# PCB_Assignment.net
KiCad netlist of a schematic drawn in EAGLE
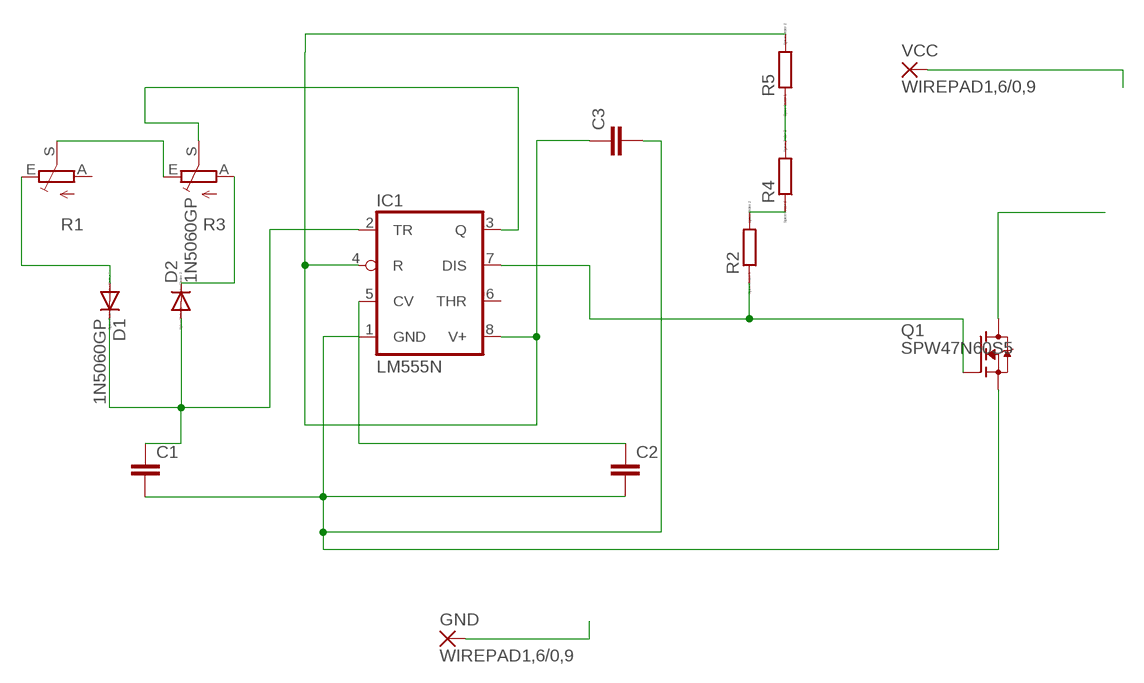
[diagram p0: schematic, sheet 1]

(export (version "E")
  (design (tool "Eeschema 10.0.6"))
  (components
    (comp (ref "C1")
      (value "C2.5/2")
      (footprint "eagle-import:C2.5-2")
      (libsource (lib "eagle-import") (part "C2.5/2"))
    )
    (comp (ref "C2")
      (value "C2.5/2")
      (footprint "eagle-import:C2.5-2")
      (libsource (lib "eagle-import") (part "C2.5/2"))
    )
    (comp (ref "C3")
      (value "C2.5/2")
      (footprint "eagle-import:C2.5-2")
      (libsource (lib "eagle-import") (part "C2.5/2"))
    )
    (comp (ref "D1")
      (value "1N5060GP")
      (footprint "eagle-import:DO15-12")
      (libsource (lib "eagle-import") (part "1N5060GP"))
    )
    (comp (ref "D2")
      (value "1N5060GP")
      (footprint "eagle-import:DO15-12")
      (libsource (lib "eagle-import") (part "1N5060GP"))
    )
    (comp (ref "GND")
      (value "WIREPAD1,6/0,9")
      (footprint "eagle-import:1,6_0,9")
      (libsource (lib "eagle-import") (part "WIREPAD1,6/0,9"))
    )
    (comp (ref "IC1")
      (value "LM555N")
      (footprint "eagle-import:DIL08")
      (libsource (lib "eagle-import") (part "555NLM"))
    )
    (comp (ref "Q1")
      (value "SPW47N60S5")
      (footprint "eagle-import:P-TO247")
      (libsource (lib "eagle-import") (part "SPW47N60S5"))
    )
    (comp (ref "R1")
      (value "TRIM_EU-B64Y")
      (footprint "eagle-import:B64Y")
      (libsource (lib "eagle-import") (part "TRIM_EU-B64Y"))
    )
    (comp (ref "R2")
      (value "R0204/7")
      (footprint "eagle-import:0204_7")
      (libsource (lib "eagle-import") (part "R0204/7"))
    )
    (comp (ref "R3")
      (value "TRIM_EU-B64Y")
      (footprint "eagle-import:B64Y")
      (libsource (lib "eagle-import") (part "TRIM_EU-B64Y"))
    )
    (comp (ref "R4")
      (value "R0204/7")
      (footprint "eagle-import:0204_7")
      (libsource (lib "eagle-import") (part "R0204/7"))
    )
    (comp (ref "R5")
      (value "R0204/7")
      (footprint "eagle-import:0204_7")
      (libsource (lib "eagle-import") (part "R0204/7"))
    )
    (comp (ref "VCC")
      (value "WIREPAD1,6/0,9")
      (footprint "eagle-import:1,6_0,9")
      (libsource (lib "eagle-import") (part "WIREPAD1,6/0,9"))
    )
  )
  (nets
    (net (code "1") (name "/GND") (class "Default")
      (node (ref "C1") (pin "2") (pinfunction "2_2") (pintype "passive"))
      (node (ref "C2") (pin "2") (pinfunction "2_2") (pintype "passive"))
      (node (ref "C3") (pin "2") (pinfunction "2_2") (pintype "passive"))
      (node (ref "GND") (pin "1") (pinfunction "P_1") (pintype "passive"))
      (node (ref "IC1") (pin "1") (pinfunction "GND_1") (pintype "power_in"))
      (node (ref "Q1") (pin "3") (pinfunction "S_3") (pintype "passive"))
    )
    (net (code "2") (name "/VCC") (class "Default")
      (node (ref "C3") (pin "1") (pinfunction "1_1") (pintype "passive"))
      (node (ref "IC1") (pin "4") (pinfunction "R_4") (pintype "input"))
      (node (ref "IC1") (pin "8") (pinfunction "V+_8") (pintype "power_in"))
      (node (ref "R5") (pin "2") (pinfunction "2_2") (pintype "passive"))
      (node (ref "VCC") (pin "1") (pinfunction "P_1") (pintype "passive"))
    )
    (net (code "3") (name "Net-(D1-PadA)") (class "Default")
      (node (ref "D1") (pin "A") (pinfunction "A_A") (pintype "passive"))
      (node (ref "R1") (pin "E") (pinfunction "E_E") (pintype "passive"))
    )
    (net (code "4") (name "Net-(D2-PadC)") (class "Default")
      (node (ref "D2") (pin "C") (pinfunction "C_C") (pintype "passive"))
      (node (ref "R3") (pin "A") (pinfunction "A_A") (pintype "passive"))
    )
    (net (code "5") (name "Net-(IC1-CV)") (class "Default")
      (node (ref "C2") (pin "1") (pinfunction "1_1") (pintype "passive"))
      (node (ref "IC1") (pin "5") (pinfunction "CV_5") (pintype "input"))
    )
    (net (code "6") (name "Net-(IC1-DIS)") (class "Default")
      (node (ref "IC1") (pin "7") (pinfunction "DIS_7") (pintype "input"))
      (node (ref "Q1") (pin "1") (pinfunction "G_1") (pintype "passive"))
      (node (ref "R2") (pin "1") (pinfunction "1_1") (pintype "passive"))
    )
    (net (code "7") (name "Net-(IC1-Q)") (class "Default")
      (node (ref "IC1") (pin "3") (pinfunction "Q_3") (pintype "output"))
      (node (ref "R3") (pin "S") (pinfunction "S_S") (pintype "passive"))
    )
    (net (code "8") (name "Net-(IC1-TR)") (class "Default")
      (node (ref "C1") (pin "1") (pinfunction "1_1") (pintype "passive"))
      (node (ref "D1") (pin "C") (pinfunction "C_C") (pintype "passive"))
      (node (ref "D2") (pin "A") (pinfunction "A_A") (pintype "passive"))
      (node (ref "IC1") (pin "2") (pinfunction "TR_2") (pintype "input"))
    )
    (net (code "9") (name "Net-(R1-PadS)") (class "Default")
      (node (ref "R1") (pin "S") (pinfunction "S_S") (pintype "passive"))
      (node (ref "R3") (pin "E") (pinfunction "E_E") (pintype "passive"))
    )
    (net (code "10") (name "Net-(R2-Pad2)") (class "Default")
      (node (ref "R2") (pin "2") (pinfunction "2_2") (pintype "passive"))
      (node (ref "R4") (pin "1") (pinfunction "1_1") (pintype "passive"))
    )
    (net (code "11") (name "Net-(R4-Pad2)") (class "Default")
      (node (ref "R4") (pin "2") (pinfunction "2_2") (pintype "passive"))
      (node (ref "R5") (pin "1") (pinfunction "1_1") (pintype "passive"))
    )
    (net (code "12") (name "unconnected-(IC1-THR-Pad6)") (class "Default")
      (node (ref "IC1") (pin "6") (pinfunction "THR_6") (pintype "input"))
    )
    (net (code "13") (name "unconnected-(Q1-D-Pad2)") (class "Default")
      (node (ref "Q1") (pin "2") (pinfunction "D_2") (pintype "passive"))
    )
    (net (code "14") (name "unconnected-(R1-PadA)") (class "Default")
      (node (ref "R1") (pin "A") (pinfunction "A_A") (pintype "passive"))
    )
  )
)
